# peripheral_devices_power_controller_boar.net
KiCad netlist of a schematic drawn in EAGLE
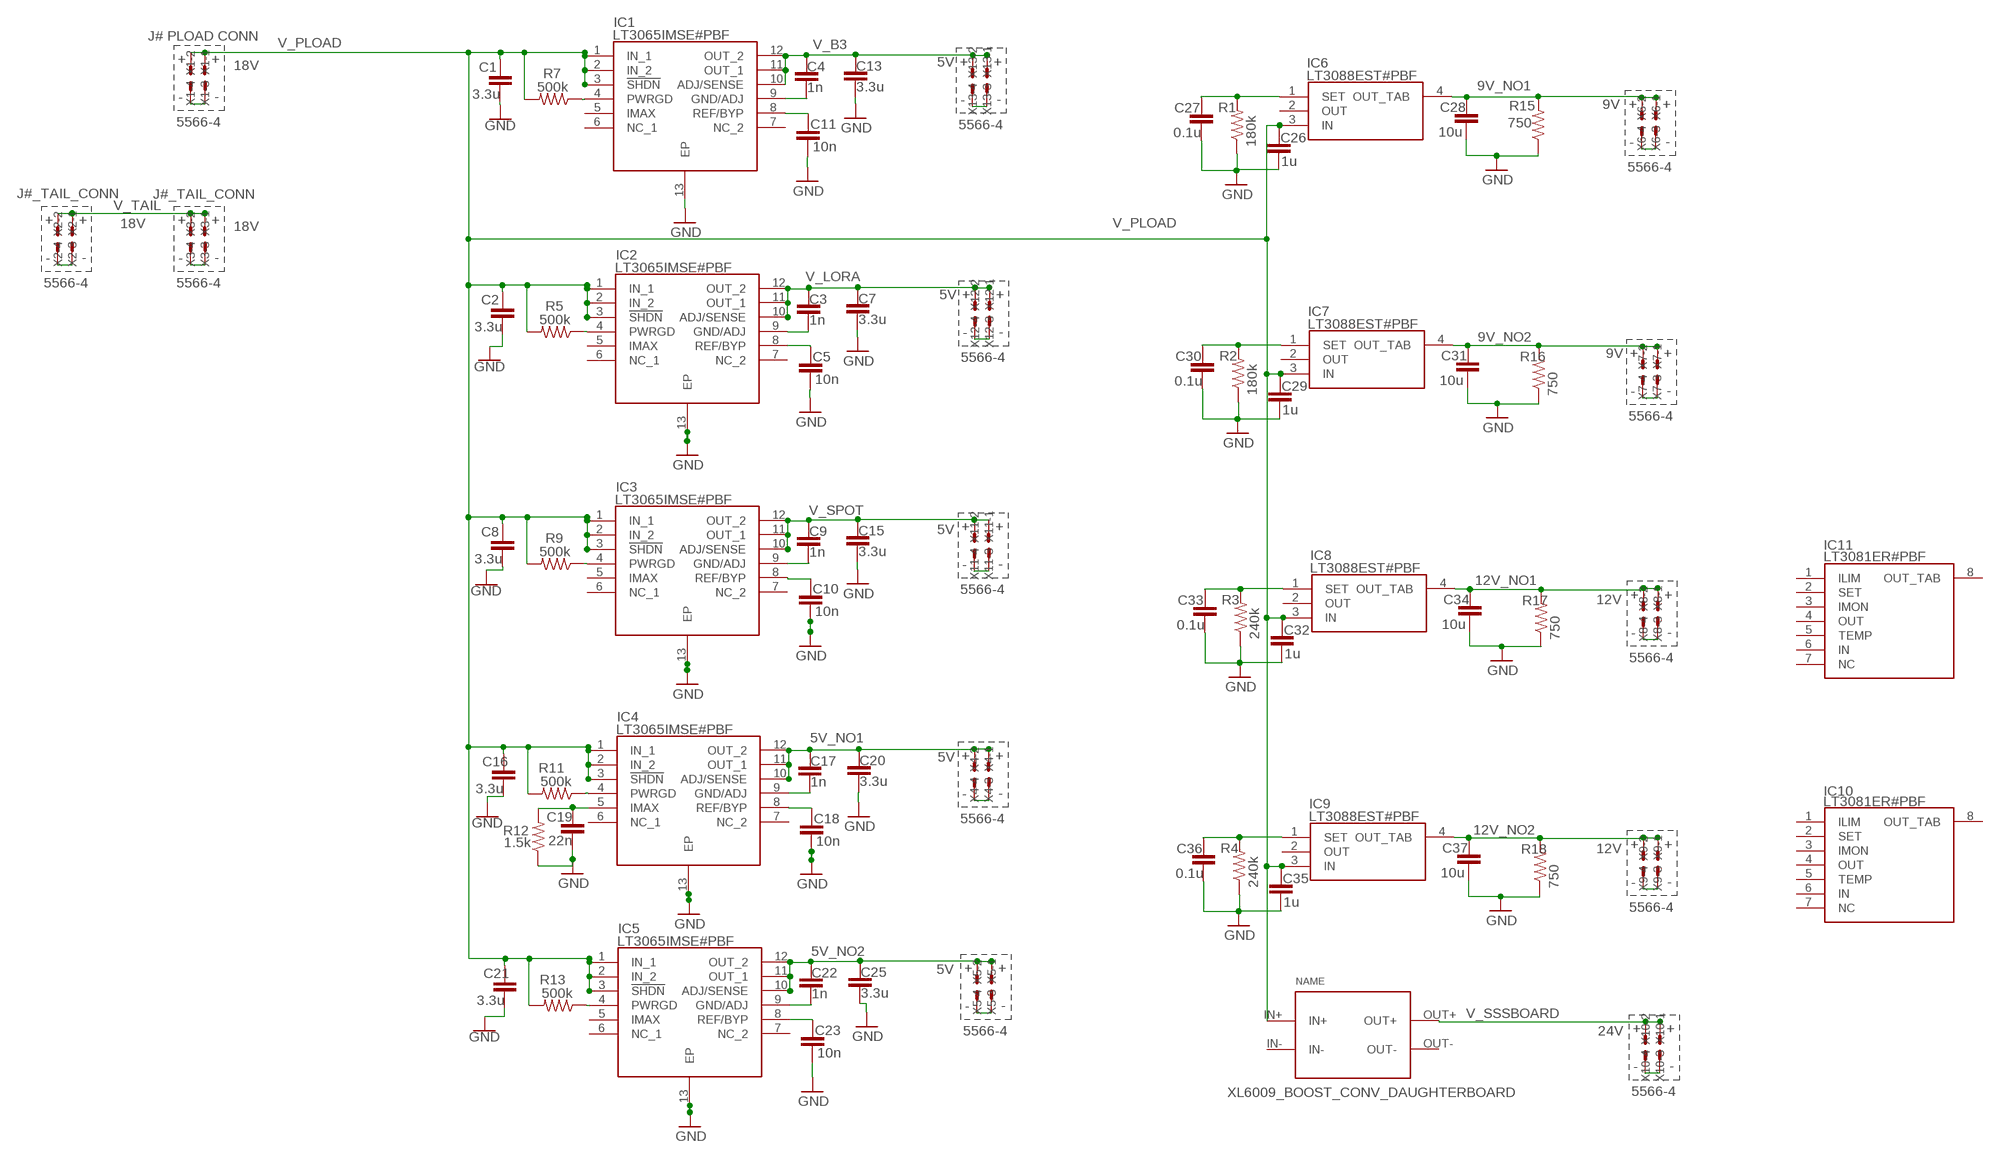
[diagram p0: schematic, sheet 1]

(export (version "E")
  (design (tool "Eeschema 10.0.6"))
  (components
    (comp (ref "C1")
      (value "3.3u")
      (footprint "eagle-import:C0805K")
      (libsource (lib "eagle-import") (part "C-EUC0805K"))
    )
    (comp (ref "C2")
      (value "3.3u")
      (footprint "eagle-import:C0805K")
      (libsource (lib "eagle-import") (part "C-EUC0805K"))
    )
    (comp (ref "C3")
      (value "1n")
      (footprint "eagle-import:C0805K")
      (libsource (lib "eagle-import") (part "C-EUC0805K"))
    )
    (comp (ref "C4")
      (value "1n")
      (footprint "eagle-import:C0805K")
      (libsource (lib "eagle-import") (part "C-EUC0805K"))
    )
    (comp (ref "C5")
      (value "10n")
      (footprint "eagle-import:C0805K")
      (libsource (lib "eagle-import") (part "C-EUC0805K"))
    )
    (comp (ref "C7")
      (value "3.3u")
      (footprint "eagle-import:C0805K")
      (libsource (lib "eagle-import") (part "C-EUC0805K"))
    )
    (comp (ref "C8")
      (value "3.3u")
      (footprint "eagle-import:C0805K")
      (libsource (lib "eagle-import") (part "C-EUC0805K"))
    )
    (comp (ref "C9")
      (value "1n")
      (footprint "eagle-import:C0805K")
      (libsource (lib "eagle-import") (part "C-EUC0805K"))
    )
    (comp (ref "C10")
      (value "10n")
      (footprint "eagle-import:C0805K")
      (libsource (lib "eagle-import") (part "C-EUC0805K"))
    )
    (comp (ref "C11")
      (value "10n")
      (footprint "eagle-import:C0805K")
      (libsource (lib "eagle-import") (part "C-EUC0805K"))
    )
    (comp (ref "C13")
      (value "3.3u")
      (footprint "eagle-import:C0805K")
      (libsource (lib "eagle-import") (part "C-EUC0805K"))
    )
    (comp (ref "C15")
      (value "3.3u")
      (footprint "eagle-import:C0805K")
      (libsource (lib "eagle-import") (part "C-EUC0805K"))
    )
    (comp (ref "C16")
      (value "3.3u")
      (footprint "eagle-import:C0805K")
      (libsource (lib "eagle-import") (part "C-EUC0805K"))
    )
    (comp (ref "C17")
      (value "1n")
      (footprint "eagle-import:C0805K")
      (libsource (lib "eagle-import") (part "C-EUC0805K"))
    )
    (comp (ref "C18")
      (value "10n")
      (footprint "eagle-import:C0805K")
      (libsource (lib "eagle-import") (part "C-EUC0805K"))
    )
    (comp (ref "C19")
      (value "22n")
      (footprint "eagle-import:C0805K")
      (libsource (lib "eagle-import") (part "C-EUC0805K"))
    )
    (comp (ref "C20")
      (value "3.3u")
      (footprint "eagle-import:C0805K")
      (libsource (lib "eagle-import") (part "C-EUC0805K"))
    )
    (comp (ref "C21")
      (value "3.3u")
      (footprint "eagle-import:C0805K")
      (libsource (lib "eagle-import") (part "C-EUC0805K"))
    )
    (comp (ref "C22")
      (value "1n")
      (footprint "eagle-import:C0805K")
      (libsource (lib "eagle-import") (part "C-EUC0805K"))
    )
    (comp (ref "C23")
      (value "10n")
      (footprint "eagle-import:C0805K")
      (libsource (lib "eagle-import") (part "C-EUC0805K"))
    )
    (comp (ref "C25")
      (value "3.3u")
      (footprint "eagle-import:C0805K")
      (libsource (lib "eagle-import") (part "C-EUC0805K"))
    )
    (comp (ref "C26")
      (value "1u")
      (footprint "eagle-import:C0805K")
      (libsource (lib "eagle-import") (part "C-EUC0805K"))
    )
    (comp (ref "C27")
      (value "0.1u")
      (footprint "eagle-import:C0805K")
      (libsource (lib "eagle-import") (part "C-EUC0805K"))
    )
    (comp (ref "C28")
      (value "10u")
      (footprint "eagle-import:C0805K")
      (libsource (lib "eagle-import") (part "C-EUC0805K"))
    )
    (comp (ref "C29")
      (value "1u")
      (footprint "eagle-import:C0805K")
      (libsource (lib "eagle-import") (part "C-EUC0805K"))
    )
    (comp (ref "C30")
      (value "0.1u")
      (footprint "eagle-import:C0805K")
      (libsource (lib "eagle-import") (part "C-EUC0805K"))
    )
    (comp (ref "C31")
      (value "10u")
      (footprint "eagle-import:C0805K")
      (libsource (lib "eagle-import") (part "C-EUC0805K"))
    )
    (comp (ref "C32")
      (value "1u")
      (footprint "eagle-import:C0805K")
      (libsource (lib "eagle-import") (part "C-EUC0805K"))
    )
    (comp (ref "C33")
      (value "0.1u")
      (footprint "eagle-import:C0805K")
      (libsource (lib "eagle-import") (part "C-EUC0805K"))
    )
    (comp (ref "C34")
      (value "10u")
      (footprint "eagle-import:C0805K")
      (libsource (lib "eagle-import") (part "C-EUC0805K"))
    )
    (comp (ref "C35")
      (value "1u")
      (footprint "eagle-import:C0805K")
      (libsource (lib "eagle-import") (part "C-EUC0805K"))
    )
    (comp (ref "C36")
      (value "0.1u")
      (footprint "eagle-import:C0805K")
      (libsource (lib "eagle-import") (part "C-EUC0805K"))
    )
    (comp (ref "C37")
      (value "10u")
      (footprint "eagle-import:C0805K")
      (libsource (lib "eagle-import") (part "C-EUC0805K"))
    )
    (comp (ref "IC1")
      (value "LT3065IMSE#PBF")
      (footprint "eagle-import:SOP65P490X110-13N")
      (fields (field (name "MOUSER_PART_NUMBER") "584-LT3065IMSE#PBF"))
      (libsource (lib "eagle-import") (part "LT3065IMSE#PBF"))
    )
    (comp (ref "IC2")
      (value "LT3065IMSE#PBF")
      (footprint "eagle-import:SOP65P490X110-13N")
      (fields (field (name "MOUSER_PART_NUMBER") "584-LT3065IMSE#PBF"))
      (libsource (lib "eagle-import") (part "LT3065IMSE#PBF"))
    )
    (comp (ref "IC3")
      (value "LT3065IMSE#PBF")
      (footprint "eagle-import:SOP65P490X110-13N")
      (fields (field (name "MOUSER_PART_NUMBER") "584-LT3065IMSE#PBF"))
      (libsource (lib "eagle-import") (part "LT3065IMSE#PBF"))
    )
    (comp (ref "IC4")
      (value "LT3065IMSE#PBF")
      (footprint "eagle-import:SOP65P490X110-13N")
      (fields (field (name "MOUSER_PART_NUMBER") "584-LT3065IMSE#PBF"))
      (libsource (lib "eagle-import") (part "LT3065IMSE#PBF"))
    )
    (comp (ref "IC5")
      (value "LT3065IMSE#PBF")
      (footprint "eagle-import:SOP65P490X110-13N")
      (fields (field (name "MOUSER_PART_NUMBER") "584-LT3065IMSE#PBF"))
      (libsource (lib "eagle-import") (part "LT3065IMSE#PBF"))
    )
    (comp (ref "IC6")
      (value "LT3088EST#PBF")
      (footprint "eagle-import:SOT230P700X180-4N")
      (fields (field (name "MOUSER_PART_NUMBER") "584-LT3088EST#PBF"))
      (libsource (lib "eagle-import") (part "LT3088EST#PBF"))
    )
    (comp (ref "IC7")
      (value "LT3088EST#PBF")
      (footprint "eagle-import:SOT230P700X180-4N")
      (fields (field (name "MOUSER_PART_NUMBER") "584-LT3088EST#PBF"))
      (libsource (lib "eagle-import") (part "LT3088EST#PBF"))
    )
    (comp (ref "IC8")
      (value "LT3088EST#PBF")
      (footprint "eagle-import:SOT230P700X180-4N")
      (fields (field (name "MOUSER_PART_NUMBER") "584-LT3088EST#PBF"))
      (libsource (lib "eagle-import") (part "LT3088EST#PBF"))
    )
    (comp (ref "IC9")
      (value "LT3088EST#PBF")
      (footprint "eagle-import:SOT230P700X180-4N")
      (fields (field (name "MOUSER_PART_NUMBER") "584-LT3088EST#PBF"))
      (libsource (lib "eagle-import") (part "LT3088EST#PBF"))
    )
    (comp (ref "IC10")
      (value "LT3081ER#PBF")
      (footprint "eagle-import:TO127P1394X457-8N")
      (fields (field (name "MOUSER_PART_NUMBER") "584-LT3081ER#PBF"))
      (libsource (lib "eagle-import") (part "LT3081ER#PBF"))
    )
    (comp (ref "IC11")
      (value "LT3081ER#PBF")
      (footprint "eagle-import:TO127P1394X457-8N")
      (fields (field (name "MOUSER_PART_NUMBER") "584-LT3081ER#PBF"))
      (libsource (lib "eagle-import") (part "LT3081ER#PBF"))
    )
    (comp (ref "R1")
      (value "180k")
      (footprint "eagle-import:R0805")
      (libsource (lib "eagle-import") (part "R-US_R0805"))
    )
    (comp (ref "R2")
      (value "180k")
      (footprint "eagle-import:R0805")
      (libsource (lib "eagle-import") (part "R-US_R0805"))
    )
    (comp (ref "R3")
      (value "240k")
      (footprint "eagle-import:R0805")
      (libsource (lib "eagle-import") (part "R-US_R0805"))
    )
    (comp (ref "R4")
      (value "240k")
      (footprint "eagle-import:R0805")
      (libsource (lib "eagle-import") (part "R-US_R0805"))
    )
    (comp (ref "R5")
      (value "500k")
      (footprint "eagle-import:R0805")
      (libsource (lib "eagle-import") (part "R-US_R0805"))
    )
    (comp (ref "R7")
      (value "500k")
      (footprint "eagle-import:R0805")
      (libsource (lib "eagle-import") (part "R-US_R0805"))
    )
    (comp (ref "R9")
      (value "500k")
      (footprint "eagle-import:R0805")
      (libsource (lib "eagle-import") (part "R-US_R0805"))
    )
    (comp (ref "R11")
      (value "500k")
      (footprint "eagle-import:R0805")
      (libsource (lib "eagle-import") (part "R-US_R0805"))
    )
    (comp (ref "R12")
      (value "1.5k")
      (footprint "eagle-import:R0805")
      (libsource (lib "eagle-import") (part "R-US_R0805"))
    )
    (comp (ref "R13")
      (value "500k")
      (footprint "eagle-import:R0805")
      (libsource (lib "eagle-import") (part "R-US_R0805"))
    )
    (comp (ref "R15")
      (value "750")
      (footprint "eagle-import:R0805")
      (libsource (lib "eagle-import") (part "R-US_R0805"))
    )
    (comp (ref "R16")
      (value "750")
      (footprint "eagle-import:R0805")
      (libsource (lib "eagle-import") (part "R-US_R0805"))
    )
    (comp (ref "R17")
      (value "750")
      (footprint "eagle-import:R0805")
      (libsource (lib "eagle-import") (part "R-US_R0805"))
    )
    (comp (ref "R18")
      (value "750")
      (footprint "eagle-import:R0805")
      (libsource (lib "eagle-import") (part "R-US_R0805"))
    )
    (comp (ref "X1")
      (value "5566-4")
      (footprint "eagle-import:5566-4")
      (fields (field (name "MF") "MOLEX"))
      (libsource (lib "eagle-import") (part "5566-4"))
    )
    (comp (ref "X2")
      (value "5566-4")
      (footprint "eagle-import:5566-4")
      (fields (field (name "MF") "MOLEX"))
      (libsource (lib "eagle-import") (part "5566-4"))
    )
    (comp (ref "X3")
      (value "5566-4")
      (footprint "eagle-import:5566-4")
      (fields (field (name "MF") "MOLEX"))
      (libsource (lib "eagle-import") (part "5566-4"))
    )
    (comp (ref "X4")
      (value "5566-4")
      (footprint "eagle-import:5566-4")
      (fields (field (name "MF") "MOLEX"))
      (libsource (lib "eagle-import") (part "5566-4"))
    )
    (comp (ref "X5")
      (value "5566-4")
      (footprint "eagle-import:5566-4")
      (fields (field (name "MF") "MOLEX"))
      (libsource (lib "eagle-import") (part "5566-4"))
    )
    (comp (ref "X6")
      (value "5566-4")
      (footprint "eagle-import:5566-4")
      (fields (field (name "MF") "MOLEX"))
      (libsource (lib "eagle-import") (part "5566-4"))
    )
    (comp (ref "X7")
      (value "5566-4")
      (footprint "eagle-import:5566-4")
      (fields (field (name "MF") "MOLEX"))
      (libsource (lib "eagle-import") (part "5566-4"))
    )
    (comp (ref "X8")
      (value "5566-4")
      (footprint "eagle-import:5566-4")
      (fields (field (name "MF") "MOLEX"))
      (libsource (lib "eagle-import") (part "5566-4"))
    )
    (comp (ref "X9")
      (value "5566-4")
      (footprint "eagle-import:5566-4")
      (fields (field (name "MF") "MOLEX"))
      (libsource (lib "eagle-import") (part "5566-4"))
    )
    (comp (ref "X10")
      (value "5566-4")
      (footprint "eagle-import:5566-4")
      (fields (field (name "MF") "MOLEX"))
      (libsource (lib "eagle-import") (part "5566-4"))
    )
    (comp (ref "X11")
      (value "5566-4")
      (footprint "eagle-import:5566-4")
      (fields (field (name "MF") "MOLEX"))
      (libsource (lib "eagle-import") (part "5566-4"))
    )
    (comp (ref "X12")
      (value "5566-4")
      (footprint "eagle-import:5566-4")
      (fields (field (name "MF") "MOLEX"))
      (libsource (lib "eagle-import") (part "5566-4"))
    )
    (comp (ref "X13")
      (value "5566-4")
      (footprint "eagle-import:5566-4")
      (fields (field (name "MF") "MOLEX"))
      (libsource (lib "eagle-import") (part "5566-4"))
    )
    (comp (ref "XL6009_BOOST_CONV_DAUGHTERBOARD")
      (value "CP8-ADJ")
      (footprint "eagle-import:CP8-ADJ")
      (libsource (lib "eagle-import") (part "CP8-ADJ"))
    )
  )
  (nets
    (net (code "1") (name "/5V_NO1") (class "Default")
      (node (ref "C17") (pin "1") (pinfunction "1_1") (pintype "passive"))
      (node (ref "C20") (pin "1") (pinfunction "1_1") (pintype "passive"))
      (node (ref "IC4") (pin "10") (pinfunction "ADJ/SENSE_10") (pintype "bidirectional"))
      (node (ref "IC4") (pin "11") (pinfunction "OUT_1_11") (pintype "bidirectional"))
      (node (ref "IC4") (pin "12") (pinfunction "OUT_2_12") (pintype "bidirectional"))
      (node (ref "X4") (pin "3") (pinfunction "S_3") (pintype "passive"))
      (node (ref "X4") (pin "4") (pinfunction "S_4") (pintype "passive"))
    )
    (net (code "2") (name "/5V_NO2") (class "Default")
      (node (ref "C22") (pin "1") (pinfunction "1_1") (pintype "passive"))
      (node (ref "C25") (pin "1") (pinfunction "1_1") (pintype "passive"))
      (node (ref "IC5") (pin "10") (pinfunction "ADJ/SENSE_10") (pintype "bidirectional"))
      (node (ref "IC5") (pin "11") (pinfunction "OUT_1_11") (pintype "bidirectional"))
      (node (ref "IC5") (pin "12") (pinfunction "OUT_2_12") (pintype "bidirectional"))
      (node (ref "X5") (pin "3") (pinfunction "S_3") (pintype "passive"))
      (node (ref "X5") (pin "4") (pinfunction "S_4") (pintype "passive"))
    )
    (net (code "3") (name "/9V_NO1") (class "Default")
      (node (ref "C28") (pin "1") (pinfunction "1_1") (pintype "passive"))
      (node (ref "IC6") (pin "4") (pinfunction "OUT_TAB_4") (pintype "output"))
      (node (ref "R15") (pin "2") (pinfunction "2_2") (pintype "passive"))
      (node (ref "X6") (pin "3") (pinfunction "S_3") (pintype "passive"))
      (node (ref "X6") (pin "4") (pinfunction "S_4") (pintype "passive"))
    )
    (net (code "4") (name "/9V_NO2") (class "Default")
      (node (ref "C31") (pin "1") (pinfunction "1_1") (pintype "passive"))
      (node (ref "IC7") (pin "4") (pinfunction "OUT_TAB_4") (pintype "output"))
      (node (ref "R16") (pin "2") (pinfunction "2_2") (pintype "passive"))
      (node (ref "X7") (pin "3") (pinfunction "S_3") (pintype "passive"))
      (node (ref "X7") (pin "4") (pinfunction "S_4") (pintype "passive"))
    )
    (net (code "5") (name "/12V_NO1") (class "Default")
      (node (ref "C34") (pin "1") (pinfunction "1_1") (pintype "passive"))
      (node (ref "IC8") (pin "4") (pinfunction "OUT_TAB_4") (pintype "output"))
      (node (ref "R17") (pin "2") (pinfunction "2_2") (pintype "passive"))
      (node (ref "X8") (pin "3") (pinfunction "S_3") (pintype "passive"))
      (node (ref "X8") (pin "4") (pinfunction "S_4") (pintype "passive"))
    )
    (net (code "6") (name "/12V_NO2") (class "Default")
      (node (ref "C37") (pin "1") (pinfunction "1_1") (pintype "passive"))
      (node (ref "IC9") (pin "4") (pinfunction "OUT_TAB_4") (pintype "output"))
      (node (ref "R18") (pin "2") (pinfunction "2_2") (pintype "passive"))
      (node (ref "X9") (pin "3") (pinfunction "S_3") (pintype "passive"))
      (node (ref "X9") (pin "4") (pinfunction "S_4") (pintype "passive"))
    )
    (net (code "7") (name "/V_B3") (class "Default")
      (node (ref "C13") (pin "1") (pinfunction "1_1") (pintype "passive"))
      (node (ref "C4") (pin "1") (pinfunction "1_1") (pintype "passive"))
      (node (ref "IC1") (pin "10") (pinfunction "ADJ/SENSE_10") (pintype "bidirectional"))
      (node (ref "IC1") (pin "11") (pinfunction "OUT_1_11") (pintype "bidirectional"))
      (node (ref "IC1") (pin "12") (pinfunction "OUT_2_12") (pintype "bidirectional"))
      (node (ref "X13") (pin "3") (pinfunction "S_3") (pintype "passive"))
      (node (ref "X13") (pin "4") (pinfunction "S_4") (pintype "passive"))
    )
    (net (code "8") (name "/V_LORA") (class "Default")
      (node (ref "C3") (pin "1") (pinfunction "1_1") (pintype "passive"))
      (node (ref "C7") (pin "1") (pinfunction "1_1") (pintype "passive"))
      (node (ref "IC2") (pin "10") (pinfunction "ADJ/SENSE_10") (pintype "bidirectional"))
      (node (ref "IC2") (pin "11") (pinfunction "OUT_1_11") (pintype "bidirectional"))
      (node (ref "IC2") (pin "12") (pinfunction "OUT_2_12") (pintype "bidirectional"))
      (node (ref "X12") (pin "3") (pinfunction "S_3") (pintype "passive"))
      (node (ref "X12") (pin "4") (pinfunction "S_4") (pintype "passive"))
    )
    (net (code "9") (name "/V_PLOAD") (class "Default")
      (node (ref "C1") (pin "1") (pinfunction "1_1") (pintype "passive"))
      (node (ref "C16") (pin "1") (pinfunction "1_1") (pintype "passive"))
      (node (ref "C2") (pin "1") (pinfunction "1_1") (pintype "passive"))
      (node (ref "C21") (pin "1") (pinfunction "1_1") (pintype "passive"))
      (node (ref "C26") (pin "1") (pinfunction "1_1") (pintype "passive"))
      (node (ref "C29") (pin "1") (pinfunction "1_1") (pintype "passive"))
      (node (ref "C32") (pin "1") (pinfunction "1_1") (pintype "passive"))
      (node (ref "C35") (pin "1") (pinfunction "1_1") (pintype "passive"))
      (node (ref "C8") (pin "1") (pinfunction "1_1") (pintype "passive"))
      (node (ref "IC1") (pin "1") (pinfunction "IN_1_1") (pintype "bidirectional"))
      (node (ref "IC1") (pin "2") (pinfunction "IN_2_2") (pintype "bidirectional"))
      (node (ref "IC1") (pin "3") (pinfunction "~{SHDN}_3") (pintype "bidirectional"))
      (node (ref "IC2") (pin "1") (pinfunction "IN_1_1") (pintype "bidirectional"))
      (node (ref "IC2") (pin "2") (pinfunction "IN_2_2") (pintype "bidirectional"))
      (node (ref "IC2") (pin "3") (pinfunction "~{SHDN}_3") (pintype "bidirectional"))
      (node (ref "IC3") (pin "1") (pinfunction "IN_1_1") (pintype "bidirectional"))
      (node (ref "IC3") (pin "2") (pinfunction "IN_2_2") (pintype "bidirectional"))
      (node (ref "IC3") (pin "3") (pinfunction "~{SHDN}_3") (pintype "bidirectional"))
      (node (ref "IC4") (pin "1") (pinfunction "IN_1_1") (pintype "bidirectional"))
      (node (ref "IC4") (pin "2") (pinfunction "IN_2_2") (pintype "bidirectional"))
      (node (ref "IC4") (pin "3") (pinfunction "~{SHDN}_3") (pintype "bidirectional"))
      (node (ref "IC5") (pin "1") (pinfunction "IN_1_1") (pintype "bidirectional"))
      (node (ref "IC5") (pin "2") (pinfunction "IN_2_2") (pintype "bidirectional"))
      (node (ref "IC5") (pin "3") (pinfunction "~{SHDN}_3") (pintype "bidirectional"))
      (node (ref "IC6") (pin "3") (pinfunction "IN_3") (pintype "input"))
      (node (ref "IC7") (pin "3") (pinfunction "IN_3") (pintype "input"))
      (node (ref "IC8") (pin "3") (pinfunction "IN_3") (pintype "input"))
      (node (ref "IC9") (pin "3") (pinfunction "IN_3") (pintype "input"))
      (node (ref "R11") (pin "2") (pinfunction "2_2") (pintype "passive"))
      (node (ref "R13") (pin "2") (pinfunction "2_2") (pintype "passive"))
      (node (ref "R5") (pin "2") (pinfunction "2_2") (pintype "passive"))
      (node (ref "R7") (pin "2") (pinfunction "2_2") (pintype "passive"))
      (node (ref "R9") (pin "2") (pinfunction "2_2") (pintype "passive"))
      (node (ref "X1") (pin "3") (pinfunction "S_3") (pintype "passive"))
      (node (ref "X1") (pin "4") (pinfunction "S_4") (pintype "passive"))
      (node (ref "XL6009_BOOST_CONV_DAUGHTERBOARD") (pin "IN+") (pinfunction "IN+_IN+") (pintype "passive"))
    )
    (net (code "10") (name "/V_SPOT") (class "Default")
      (node (ref "C15") (pin "1") (pinfunction "1_1") (pintype "passive"))
      (node (ref "C9") (pin "1") (pinfunction "1_1") (pintype "passive"))
      (node (ref "IC3") (pin "10") (pinfunction "ADJ/SENSE_10") (pintype "bidirectional"))
      (node (ref "IC3") (pin "11") (pinfunction "OUT_1_11") (pintype "bidirectional"))
      (node (ref "IC3") (pin "12") (pinfunction "OUT_2_12") (pintype "bidirectional"))
      (node (ref "X11") (pin "3") (pinfunction "S_3") (pintype "passive"))
      (node (ref "X11") (pin "4") (pinfunction "S_4") (pintype "passive"))
    )
    (net (code "11") (name "/V_SSSBOARD") (class "Default")
      (node (ref "X10") (pin "3") (pinfunction "S_3") (pintype "passive"))
      (node (ref "X10") (pin "4") (pinfunction "S_4") (pintype "passive"))
      (node (ref "XL6009_BOOST_CONV_DAUGHTERBOARD") (pin "OUT+") (pinfunction "OUT+_OUT+") (pintype "passive"))
    )
    (net (code "12") (name "/V_TAIL") (class "Default")
      (node (ref "X2") (pin "3") (pinfunction "S_3") (pintype "passive"))
      (node (ref "X2") (pin "4") (pinfunction "S_4") (pintype "passive"))
      (node (ref "X3") (pin "3") (pinfunction "S_3") (pintype "passive"))
      (node (ref "X3") (pin "4") (pinfunction "S_4") (pintype "passive"))
    )
    (net (code "13") (name "GND") (class "Default")
      (node (ref "C1") (pin "2") (pinfunction "2_2") (pintype "passive"))
      (node (ref "C10") (pin "2") (pinfunction "2_2") (pintype "passive"))
      (node (ref "C11") (pin "2") (pinfunction "2_2") (pintype "passive"))
      (node (ref "C13") (pin "2") (pinfunction "2_2") (pintype "passive"))
      (node (ref "C15") (pin "2") (pinfunction "2_2") (pintype "passive"))
      (node (ref "C16") (pin "2") (pinfunction "2_2") (pintype "passive"))
      (node (ref "C18") (pin "2") (pinfunction "2_2") (pintype "passive"))
      (node (ref "C19") (pin "2") (pinfunction "2_2") (pintype "passive"))
      (node (ref "C2") (pin "2") (pinfunction "2_2") (pintype "passive"))
      (node (ref "C20") (pin "2") (pinfunction "2_2") (pintype "passive"))
      (node (ref "C21") (pin "2") (pinfunction "2_2") (pintype "passive"))
      (node (ref "C23") (pin "2") (pinfunction "2_2") (pintype "passive"))
      (node (ref "C25") (pin "2") (pinfunction "2_2") (pintype "passive"))
      (node (ref "C26") (pin "2") (pinfunction "2_2") (pintype "passive"))
      (node (ref "C27") (pin "2") (pinfunction "2_2") (pintype "passive"))
      (node (ref "C28") (pin "2") (pinfunction "2_2") (pintype "passive"))
      (node (ref "C29") (pin "2") (pinfunction "2_2") (pintype "passive"))
      (node (ref "C30") (pin "2") (pinfunction "2_2") (pintype "passive"))
      (node (ref "C31") (pin "2") (pinfunction "2_2") (pintype "passive"))
      (node (ref "C32") (pin "2") (pinfunction "2_2") (pintype "passive"))
      (node (ref "C33") (pin "2") (pinfunction "2_2") (pintype "passive"))
      (node (ref "C34") (pin "2") (pinfunction "2_2") (pintype "passive"))
      (node (ref "C35") (pin "2") (pinfunction "2_2") (pintype "passive"))
      (node (ref "C36") (pin "2") (pinfunction "2_2") (pintype "passive"))
      (node (ref "C37") (pin "2") (pinfunction "2_2") (pintype "passive"))
      (node (ref "C5") (pin "2") (pinfunction "2_2") (pintype "passive"))
      (node (ref "C7") (pin "2") (pinfunction "2_2") (pintype "passive"))
      (node (ref "C8") (pin "2") (pinfunction "2_2") (pintype "passive"))
      (node (ref "IC1") (pin "13") (pinfunction "EP_13") (pintype "bidirectional"))
      (node (ref "IC2") (pin "13") (pinfunction "EP_13") (pintype "bidirectional"))
      (node (ref "IC3") (pin "13") (pinfunction "EP_13") (pintype "bidirectional"))
      (node (ref "IC4") (pin "13") (pinfunction "EP_13") (pintype "bidirectional"))
      (node (ref "IC5") (pin "13") (pinfunction "EP_13") (pintype "bidirectional"))
      (node (ref "R1") (pin "1") (pinfunction "1_1") (pintype "passive"))
      (node (ref "R12") (pin "1") (pinfunction "1_1") (pintype "passive"))
      (node (ref "R15") (pin "1") (pinfunction "1_1") (pintype "passive"))
      (node (ref "R16") (pin "1") (pinfunction "1_1") (pintype "passive"))
      (node (ref "R17") (pin "1") (pinfunction "1_1") (pintype "passive"))
      (node (ref "R18") (pin "1") (pinfunction "1_1") (pintype "passive"))
      (node (ref "R2") (pin "1") (pinfunction "1_1") (pintype "passive"))
      (node (ref "R3") (pin "1") (pinfunction "1_1") (pintype "passive"))
      (node (ref "R4") (pin "1") (pinfunction "1_1") (pintype "passive"))
    )
    (net (code "14") (name "Net-(IC1-GND{slash}ADJ)") (class "Default")
      (node (ref "C4") (pin "2") (pinfunction "2_2") (pintype "passive"))
      (node (ref "IC1") (pin "9") (pinfunction "GND/ADJ_9") (pintype "bidirectional"))
    )
    (net (code "15") (name "Net-(IC1-PWRGD)") (class "Default")
      (node (ref "IC1") (pin "4") (pinfunction "PWRGD_4") (pintype "bidirectional"))
      (node (ref "R7") (pin "1") (pinfunction "1_1") (pintype "passive"))
    )
    (net (code "16") (name "Net-(IC1-REF{slash}BYP)") (class "Default")
      (node (ref "C11") (pin "1") (pinfunction "1_1") (pintype "passive"))
      (node (ref "IC1") (pin "8") (pinfunction "REF/BYP_8") (pintype "bidirectional"))
    )
    (net (code "17") (name "Net-(IC2-GND{slash}ADJ)") (class "Default")
      (node (ref "C3") (pin "2") (pinfunction "2_2") (pintype "passive"))
      (node (ref "IC2") (pin "9") (pinfunction "GND/ADJ_9") (pintype "bidirectional"))
    )
    (net (code "18") (name "Net-(IC2-PWRGD)") (class "Default")
      (node (ref "IC2") (pin "4") (pinfunction "PWRGD_4") (pintype "bidirectional"))
      (node (ref "R5") (pin "1") (pinfunction "1_1") (pintype "passive"))
    )
    (net (code "19") (name "Net-(IC2-REF{slash}BYP)") (class "Default")
      (node (ref "C5") (pin "1") (pinfunction "1_1") (pintype "passive"))
      (node (ref "IC2") (pin "8") (pinfunction "REF/BYP_8") (pintype "bidirectional"))
    )
    (net (code "20") (name "Net-(IC3-GND{slash}ADJ)") (class "Default")
      (node (ref "C9") (pin "2") (pinfunction "2_2") (pintype "passive"))
      (node (ref "IC3") (pin "9") (pinfunction "GND/ADJ_9") (pintype "bidirectional"))
    )
    (net (code "21") (name "Net-(IC3-PWRGD)") (class "Default")
      (node (ref "IC3") (pin "4") (pinfunction "PWRGD_4") (pintype "bidirectional"))
      (node (ref "R9") (pin "1") (pinfunction "1_1") (pintype "passive"))
    )
    (net (code "22") (name "Net-(IC3-REF{slash}BYP)") (class "Default")
      (node (ref "C10") (pin "1") (pinfunction "1_1") (pintype "passive"))
      (node (ref "IC3") (pin "8") (pinfunction "REF/BYP_8") (pintype "bidirectional"))
    )
    (net (code "23") (name "Net-(IC4-GND{slash}ADJ)") (class "Default")
      (node (ref "C17") (pin "2") (pinfunction "2_2") (pintype "passive"))
      (node (ref "IC4") (pin "9") (pinfunction "GND/ADJ_9") (pintype "bidirectional"))
    )
    (net (code "24") (name "Net-(IC4-IMAX)") (class "Default")
      (node (ref "C19") (pin "1") (pinfunction "1_1") (pintype "passive"))
      (node (ref "IC4") (pin "5") (pinfunction "IMAX_5") (pintype "bidirectional"))
      (node (ref "R12") (pin "2") (pinfunction "2_2") (pintype "passive"))
    )
    (net (code "25") (name "Net-(IC4-PWRGD)") (class "Default")
      (node (ref "IC4") (pin "4") (pinfunction "PWRGD_4") (pintype "bidirectional"))
      (node (ref "R11") (pin "1") (pinfunction "1_1") (pintype "passive"))
    )
    (net (code "26") (name "Net-(IC4-REF{slash}BYP)") (class "Default")
      (node (ref "C18") (pin "1") (pinfunction "1_1") (pintype "passive"))
      (node (ref "IC4") (pin "8") (pinfunction "REF/BYP_8") (pintype "bidirectional"))
    )
    (net (code "27") (name "Net-(IC5-GND{slash}ADJ)") (class "Default")
      (node (ref "C22") (pin "2") (pinfunction "2_2") (pintype "passive"))
      (node (ref "IC5") (pin "9") (pinfunction "GND/ADJ_9") (pintype "bidirectional"))
    )
    (net (code "28") (name "Net-(IC5-PWRGD)") (class "Default")
      (node (ref "IC5") (pin "4") (pinfunction "PWRGD_4") (pintype "bidirectional"))
      (node (ref "R13") (pin "1") (pinfunction "1_1") (pintype "passive"))
    )
    (net (code "29") (name "Net-(IC5-REF{slash}BYP)") (class "Default")
      (node (ref "C23") (pin "1") (pinfunction "1_1") (pintype "passive"))
      (node (ref "IC5") (pin "8") (pinfunction "REF/BYP_8") (pintype "bidirectional"))
    )
    (net (code "30") (name "Net-(IC6-SET)") (class "Default")
      (node (ref "C27") (pin "1") (pinfunction "1_1") (pintype "passive"))
      (node (ref "IC6") (pin "1") (pinfunction "SET_1") (pintype "bidirectional"))
      (node (ref "R1") (pin "2") (pinfunction "2_2") (pintype "passive"))
    )
    (net (code "31") (name "Net-(IC7-SET)") (class "Default")
      (node (ref "C30") (pin "1") (pinfunction "1_1") (pintype "passive"))
      (node (ref "IC7") (pin "1") (pinfunction "SET_1") (pintype "bidirectional"))
      (node (ref "R2") (pin "2") (pinfunction "2_2") (pintype "passive"))
    )
    (net (code "32") (name "Net-(IC8-SET)") (class "Default")
      (node (ref "C33") (pin "1") (pinfunction "1_1") (pintype "passive"))
      (node (ref "IC8") (pin "1") (pinfunction "SET_1") (pintype "bidirectional"))
      (node (ref "R3") (pin "2") (pinfunction "2_2") (pintype "passive"))
    )
    (net (code "33") (name "Net-(IC9-SET)") (class "Default")
      (node (ref "C36") (pin "1") (pinfunction "1_1") (pintype "passive"))
      (node (ref "IC9") (pin "1") (pinfunction "SET_1") (pintype "bidirectional"))
      (node (ref "R4") (pin "2") (pinfunction "2_2") (pintype "passive"))
    )
    (net (code "34") (name "Net-(X1A-S)") (class "Default")
      (node (ref "X1") (pin "1") (pinfunction "S_1") (pintype "passive"))
      (node (ref "X1") (pin "2") (pinfunction "S_2") (pintype "passive"))
    )
    (net (code "35") (name "Net-(X2A-S)") (class "Default")
      (node (ref "X2") (pin "1") (pinfunction "S_1") (pintype "passive"))
      (node (ref "X2") (pin "2") (pinfunction "S_2") (pintype "passive"))
    )
    (net (code "36") (name "Net-(X3A-S)") (class "Default")
      (node (ref "X3") (pin "1") (pinfunction "S_1") (pintype "passive"))
      (node (ref "X3") (pin "2") (pinfunction "S_2") (pintype "passive"))
    )
    (net (code "37") (name "Net-(X4A-S)") (class "Default")
      (node (ref "X4") (pin "1") (pinfunction "S_1") (pintype "passive"))
      (node (ref "X4") (pin "2") (pinfunction "S_2") (pintype "passive"))
    )
    (net (code "38") (name "Net-(X5A-S)") (class "Default")
      (node (ref "X5") (pin "1") (pinfunction "S_1") (pintype "passive"))
      (node (ref "X5") (pin "2") (pinfunction "S_2") (pintype "passive"))
    )
    (net (code "39") (name "Net-(X6A-S)") (class "Default")
      (node (ref "X6") (pin "1") (pinfunction "S_1") (pintype "passive"))
      (node (ref "X6") (pin "2") (pinfunction "S_2") (pintype "passive"))
    )
    (net (code "40") (name "Net-(X7A-S)") (class "Default")
      (node (ref "X7") (pin "1") (pinfunction "S_1") (pintype "passive"))
      (node (ref "X7") (pin "2") (pinfunction "S_2") (pintype "passive"))
    )
    (net (code "41") (name "Net-(X8A-S)") (class "Default")
      (node (ref "X8") (pin "1") (pinfunction "S_1") (pintype "passive"))
      (node (ref "X8") (pin "2") (pinfunction "S_2") (pintype "passive"))
    )
    (net (code "42") (name "Net-(X9A-S)") (class "Default")
      (node (ref "X9") (pin "1") (pinfunction "S_1") (pintype "passive"))
      (node (ref "X9") (pin "2") (pinfunction "S_2") (pintype "passive"))
    )
    (net (code "43") (name "Net-(X10A-S)") (class "Default")
      (node (ref "X10") (pin "1") (pinfunction "S_1") (pintype "passive"))
      (node (ref "X10") (pin "2") (pinfunction "S_2") (pintype "passive"))
    )
    (net (code "44") (name "Net-(X11A-S)") (class "Default")
      (node (ref "X11") (pin "1") (pinfunction "S_1") (pintype "passive"))
      (node (ref "X11") (pin "2") (pinfunction "S_2") (pintype "passive"))
    )
    (net (code "45") (name "Net-(X12A-S)") (class "Default")
      (node (ref "X12") (pin "1") (pinfunction "S_1") (pintype "passive"))
      (node (ref "X12") (pin "2") (pinfunction "S_2") (pintype "passive"))
    )
    (net (code "46") (name "Net-(X13A-S)") (class "Default")
      (node (ref "X13") (pin "1") (pinfunction "S_1") (pintype "passive"))
      (node (ref "X13") (pin "2") (pinfunction "S_2") (pintype "passive"))
    )
    (net (code "47") (name "unconnected-(IC1-IMAX-Pad5)") (class "Default")
      (node (ref "IC1") (pin "5") (pinfunction "IMAX_5") (pintype "bidirectional"))
    )
    (net (code "48") (name "unconnected-(IC1-NC_1-Pad6)") (class "Default")
      (node (ref "IC1") (pin "6") (pinfunction "NC_1_6") (pintype "bidirectional"))
    )
    (net (code "49") (name "unconnected-(IC1-NC_2-Pad7)") (class "Default")
      (node (ref "IC1") (pin "7") (pinfunction "NC_2_7") (pintype "bidirectional"))
    )
    (net (code "50") (name "unconnected-(IC2-IMAX-Pad5)") (class "Default")
      (node (ref "IC2") (pin "5") (pinfunction "IMAX_5") (pintype "bidirectional"))
    )
    (net (code "51") (name "unconnected-(IC2-NC_1-Pad6)") (class "Default")
      (node (ref "IC2") (pin "6") (pinfunction "NC_1_6") (pintype "bidirectional"))
    )
    (net (code "52") (name "unconnected-(IC2-NC_2-Pad7)") (class "Default")
      (node (ref "IC2") (pin "7") (pinfunction "NC_2_7") (pintype "bidirectional"))
    )
    (net (code "53") (name "unconnected-(IC3-IMAX-Pad5)") (class "Default")
      (node (ref "IC3") (pin "5") (pinfunction "IMAX_5") (pintype "bidirectional"))
    )
    (net (code "54") (name "unconnected-(IC3-NC_1-Pad6)") (class "Default")
      (node (ref "IC3") (pin "6") (pinfunction "NC_1_6") (pintype "bidirectional"))
    )
    (net (code "55") (name "unconnected-(IC3-NC_2-Pad7)") (class "Default")
      (node (ref "IC3") (pin "7") (pinfunction "NC_2_7") (pintype "bidirectional"))
    )
    (net (code "56") (name "unconnected-(IC4-NC_1-Pad6)") (class "Default")
      (node (ref "IC4") (pin "6") (pinfunction "NC_1_6") (pintype "bidirectional"))
    )
    (net (code "57") (name "unconnected-(IC4-NC_2-Pad7)") (class "Default")
      (node (ref "IC4") (pin "7") (pinfunction "NC_2_7") (pintype "bidirectional"))
    )
    (net (code "58") (name "unconnected-(IC5-IMAX-Pad5)") (class "Default")
      (node (ref "IC5") (pin "5") (pinfunction "IMAX_5") (pintype "bidirectional"))
    )
    (net (code "59") (name "unconnected-(IC5-NC_1-Pad6)") (class "Default")
      (node (ref "IC5") (pin "6") (pinfunction "NC_1_6") (pintype "bidirectional"))
    )
    (net (code "60") (name "unconnected-(IC5-NC_2-Pad7)") (class "Default")
      (node (ref "IC5") (pin "7") (pinfunction "NC_2_7") (pintype "bidirectional"))
    )
    (net (code "61") (name "unconnected-(IC6-OUT-Pad2)") (class "Default")
      (node (ref "IC6") (pin "2") (pinfunction "OUT_2") (pintype "output"))
    )
    (net (code "62") (name "unconnected-(IC7-OUT-Pad2)") (class "Default")
      (node (ref "IC7") (pin "2") (pinfunction "OUT_2") (pintype "output"))
    )
    (net (code "63") (name "unconnected-(IC8-OUT-Pad2)") (class "Default")
      (node (ref "IC8") (pin "2") (pinfunction "OUT_2") (pintype "output"))
    )
    (net (code "64") (name "unconnected-(IC9-OUT-Pad2)") (class "Default")
      (node (ref "IC9") (pin "2") (pinfunction "OUT_2") (pintype "output"))
    )
    (net (code "65") (name "unconnected-(IC10-ILIM-Pad1)") (class "Default")
      (node (ref "IC10") (pin "1") (pinfunction "ILIM_1") (pintype "bidirectional"))
    )
    (net (code "66") (name "unconnected-(IC10-IMON-Pad3)") (class "Default")
      (node (ref "IC10") (pin "3") (pinfunction "IMON_3") (pintype "bidirectional"))
    )
    (net (code "67") (name "unconnected-(IC10-IN-Pad6)") (class "Default")
      (node (ref "IC10") (pin "6") (pinfunction "IN_6") (pintype "input"))
    )
    (net (code "68") (name "unconnected-(IC10-NC-Pad7)") (class "Default")
      (node (ref "IC10") (pin "7") (pinfunction "NC_7") (pintype "no_connect"))
    )
    (net (code "69") (name "unconnected-(IC10-OUT-Pad4)") (class "Default")
      (node (ref "IC10") (pin "4") (pinfunction "OUT_4") (pintype "output"))
    )
    (net (code "70") (name "unconnected-(IC10-OUT_TAB-Pad8)") (class "Default")
      (node (ref "IC10") (pin "8") (pinfunction "OUT_TAB_8") (pintype "output"))
    )
    (net (code "71") (name "unconnected-(IC10-SET-Pad2)") (class "Default")
      (node (ref "IC10") (pin "2") (pinfunction "SET_2") (pintype "bidirectional"))
    )
    (net (code "72") (name "unconnected-(IC10-TEMP-Pad5)") (class "Default")
      (node (ref "IC10") (pin "5") (pinfunction "TEMP_5") (pintype "bidirectional"))
    )
    (net (code "73") (name "unconnected-(IC11-ILIM-Pad1)") (class "Default")
      (node (ref "IC11") (pin "1") (pinfunction "ILIM_1") (pintype "bidirectional"))
    )
    (net (code "74") (name "unconnected-(IC11-IMON-Pad3)") (class "Default")
      (node (ref "IC11") (pin "3") (pinfunction "IMON_3") (pintype "bidirectional"))
    )
    (net (code "75") (name "unconnected-(IC11-IN-Pad6)") (class "Default")
      (node (ref "IC11") (pin "6") (pinfunction "IN_6") (pintype "input"))
    )
    (net (code "76") (name "unconnected-(IC11-NC-Pad7)") (class "Default")
      (node (ref "IC11") (pin "7") (pinfunction "NC_7") (pintype "no_connect"))
    )
    (net (code "77") (name "unconnected-(IC11-OUT-Pad4)") (class "Default")
      (node (ref "IC11") (pin "4") (pinfunction "OUT_4") (pintype "output"))
    )
    (net (code "78") (name "unconnected-(IC11-OUT_TAB-Pad8)") (class "Default")
      (node (ref "IC11") (pin "8") (pinfunction "OUT_TAB_8") (pintype "output"))
    )
    (net (code "79") (name "unconnected-(IC11-SET-Pad2)") (class "Default")
      (node (ref "IC11") (pin "2") (pinfunction "SET_2") (pintype "bidirectional"))
    )
    (net (code "80") (name "unconnected-(IC11-TEMP-Pad5)") (class "Default")
      (node (ref "IC11") (pin "5") (pinfunction "TEMP_5") (pintype "bidirectional"))
    )
    (net (code "81") (name "unconnected-(XL6009_BOOST_CONV_DAUGHTERBOARD-PadIN-)") (class "Default")
      (node (ref "XL6009_BOOST_CONV_DAUGHTERBOARD") (pin "IN-") (pinfunction "IN-_IN-") (pintype "passive"))
    )
    (net (code "82") (name "unconnected-(XL6009_BOOST_CONV_DAUGHTERBOARD-PadOUT-)") (class "Default")
      (node (ref "XL6009_BOOST_CONV_DAUGHTERBOARD") (pin "OUT-") (pinfunction "OUT-_OUT-") (pintype "passive"))
    )
  )
)
